# Output_Drivers1.net
KiCad netlist of a schematic drawn in Altium Designer
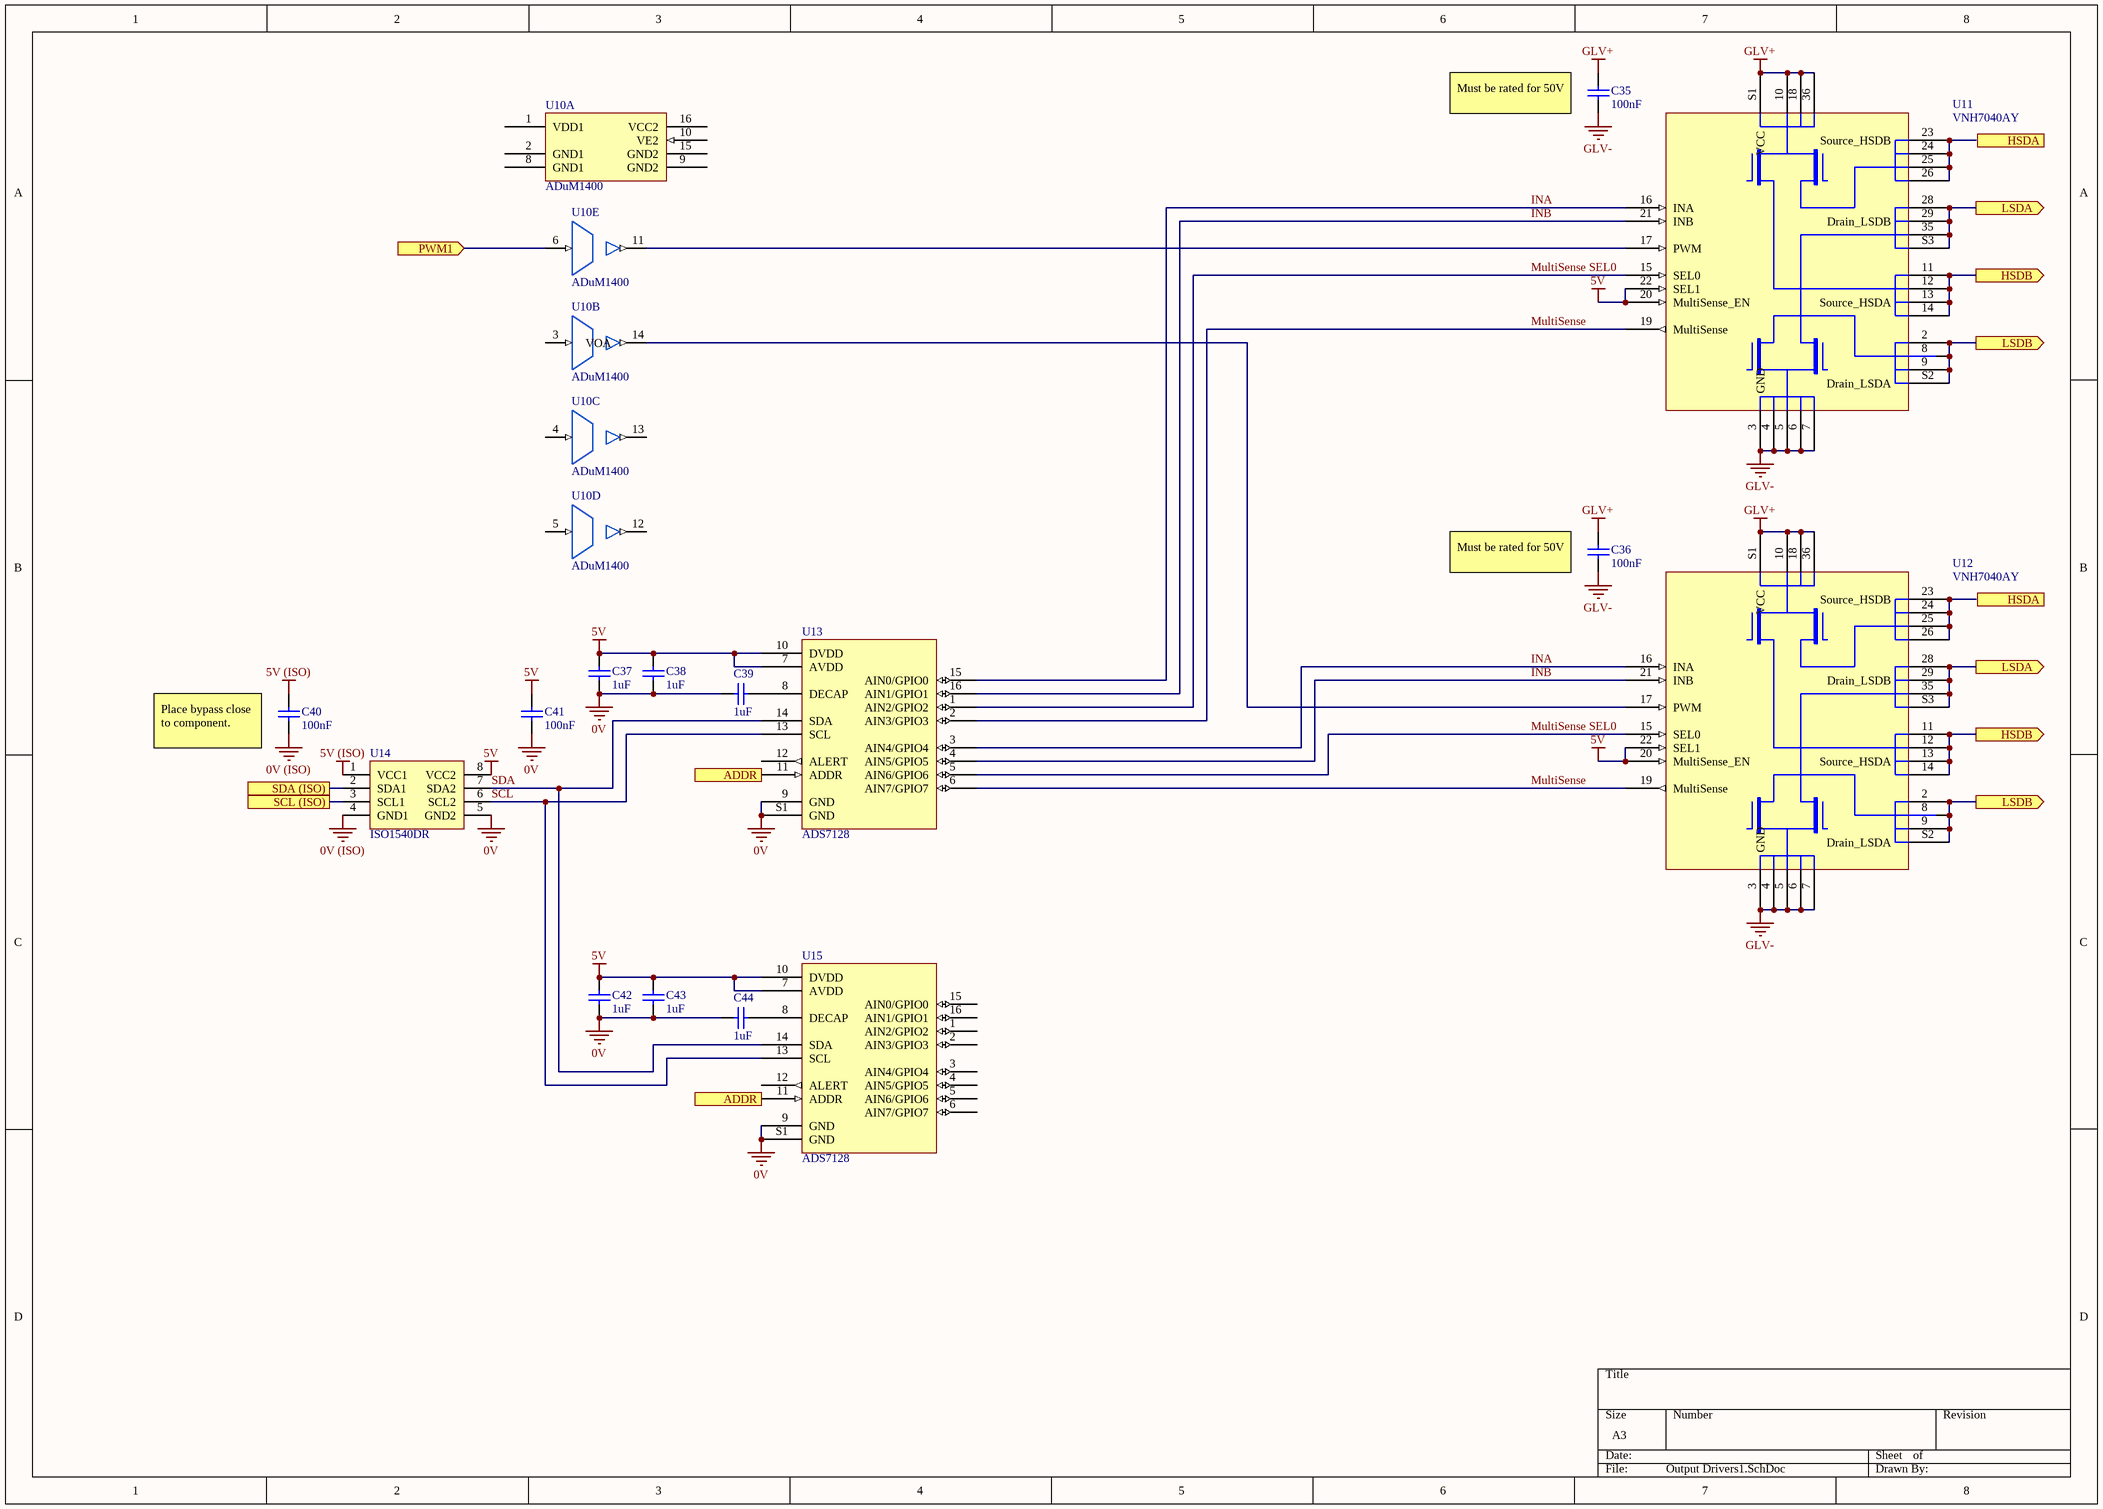
[diagram p0: Output Drivers1.SchDoc]

(export (version "E")
  (design (tool "Eeschema 10.0.6"))
  (components
    (comp (ref "C35")
      (value "100nF")
      (footprint "0805")
      (fields
        (field (name "PART NUMBER") "GCM21BR71E104KA37L")
        (field (name "TOLERANCE") "10%")
        (field (name "MANUFACTURER") "muRata")
      )
      (libsource (lib "ts_20-standard-library") (part "Capacitor"))
    )
    (comp (ref "C36")
      (value "100nF")
      (footprint "0805")
      (fields
        (field (name "PART NUMBER") "GCM21BR71E104KA37L")
        (field (name "TOLERANCE") "10%")
        (field (name "MANUFACTURER") "muRata")
      )
      (libsource (lib "ts_20-standard-library") (part "Capacitor"))
    )
    (comp (ref "C37")
      (value "1uF")
      (footprint "0805")
      (fields
        (field (name "PART NUMBER") "AC0805KKX7R8BB105")
        (field (name "TOLERANCE") "10%")
        (field (name "MANUFACTURER") "YAGEO")
      )
      (libsource (lib "ts_20-standard-library") (part "Capacitor"))
    )
    (comp (ref "C38")
      (value "1uF")
      (footprint "0805")
      (fields
        (field (name "PART NUMBER") "AC0805KKX7R8BB105")
        (field (name "TOLERANCE") "10%")
        (field (name "MANUFACTURER") "YAGEO")
      )
      (libsource (lib "ts_20-standard-library") (part "Capacitor"))
    )
    (comp (ref "C39")
      (value "1uF")
      (footprint "0805")
      (fields
        (field (name "PART NUMBER") "AC0805KKX7R8BB105")
        (field (name "TOLERANCE") "10%")
        (field (name "MANUFACTURER") "YAGEO")
      )
      (libsource (lib "ts_20-standard-library") (part "Capacitor"))
    )
    (comp (ref "C40")
      (value "100nF")
      (footprint "0805")
      (fields
        (field (name "PART NUMBER") "GCM21BR71E104KA37L")
        (field (name "TOLERANCE") "10%")
        (field (name "MANUFACTURER") "muRata")
      )
      (libsource (lib "ts_20-standard-library") (part "Capacitor"))
    )
    (comp (ref "C41")
      (value "100nF")
      (footprint "0805")
      (fields
        (field (name "PART NUMBER") "GCM21BR71E104KA37L")
        (field (name "TOLERANCE") "10%")
        (field (name "MANUFACTURER") "muRata")
      )
      (libsource (lib "ts_20-standard-library") (part "Capacitor"))
    )
    (comp (ref "C42")
      (value "1uF")
      (footprint "0805")
      (fields
        (field (name "PART NUMBER") "AC0805KKX7R8BB105")
        (field (name "TOLERANCE") "10%")
        (field (name "MANUFACTURER") "YAGEO")
      )
      (libsource (lib "ts_20-standard-library") (part "Capacitor"))
    )
    (comp (ref "C43")
      (value "1uF")
      (footprint "0805")
      (fields
        (field (name "PART NUMBER") "AC0805KKX7R8BB105")
        (field (name "TOLERANCE") "10%")
        (field (name "MANUFACTURER") "YAGEO")
      )
      (libsource (lib "ts_20-standard-library") (part "Capacitor"))
    )
    (comp (ref "C44")
      (value "1uF")
      (footprint "0805")
      (fields
        (field (name "PART NUMBER") "AC0805KKX7R8BB105")
        (field (name "TOLERANCE") "10%")
        (field (name "MANUFACTURER") "YAGEO")
      )
      (libsource (lib "ts_20-standard-library") (part "Capacitor"))
    )
    (comp (ref "U10")
      (value "ADuM1400")
      (footprint "AD 16-SOIC")
      (fields
        (field (name "MANUFACTURER") "Analog Devices")
        (field (name "DIGIKEY PART NUMBER") "ADUM1400WSRWZ-ND")
      )
      (libsource (lib "ts_20-standard-library") (part "ADuM1400"))
    )
    (comp (ref "U11")
      (value "VNH7040AY")
      (footprint "ST PowerSSO-36")
      (description "Motor Driver Power MOSFET PWM PowerSSO-36 TP")
      (fields
        (field (name "MANUFACTURER") "STMicroelectronics")
        (field (name "DIGIKEY PART NUMBER") "497-17631-1-ND")
      )
      (libsource (lib "ts_20-standard-library") (part "VNH7040AY"))
    )
    (comp (ref "U12")
      (value "VNH7040AY")
      (footprint "ST PowerSSO-36")
      (description "Motor Driver Power MOSFET PWM PowerSSO-36 TP")
      (fields
        (field (name "MANUFACTURER") "STMicroelectronics")
        (field (name "DIGIKEY PART NUMBER") "497-17631-1-ND")
      )
      (libsource (lib "ts_20-standard-library") (part "VNH7040AY"))
    )
    (comp (ref "U13")
      (value "ADS7128")
      (footprint "TI 16-WQFN")
      (description "12 Bit Analog to Digital Converter 8 Input 1 SAR 16-WQFN (3x3)")
      (fields
        (field (name "MANUFACTURER") "Texas Instruments")
        (field (name "DIGIKEY PART NUMBER") "296-ADS7128IRTERCT-ND")
      )
      (libsource (lib "ts_20-standard-library") (part "ADS7128"))
    )
    (comp (ref "U14")
      (value "ISO1540DR")
      (footprint "TI 8-SOIC")
      (description "I2C Digital Isolator (Multichannel)")
      (fields
        (field (name "MANUFACTURER") "Texas Instruments")
        (field (name "DIGIKEY PART NUMBER") "296-34871-1-ND")
      )
      (libsource (lib "ts_20-standard-library") (part "ISO1540DR"))
    )
    (comp (ref "U15")
      (value "ADS7128")
      (footprint "TI 16-WQFN")
      (description "12 Bit Analog to Digital Converter 8 Input 1 SAR 16-WQFN (3x3)")
      (fields
        (field (name "MANUFACTURER") "Texas Instruments")
        (field (name "DIGIKEY PART NUMBER") "296-ADS7128IRTERCT-ND")
      )
      (libsource (lib "ts_20-standard-library") (part "ADS7128"))
    )
  )
  (nets
    (net (code "1") (name "/ADDR") (class "Default")
      (node (ref "U13") (pin "11") (pinfunction "ADDR_11") (pintype "input"))
      (node (ref "U15") (pin "11") (pinfunction "ADDR_11") (pintype "input"))
    )
    (net (code "3") (name "/HSDB") (class "Default")
      (node (ref "U11") (pin "11") (pinfunction "Source_HSDA_11") (pintype "power_in"))
      (node (ref "U11") (pin "12") (pinfunction "Source_HSDA_12") (pintype "power_in"))
      (node (ref "U11") (pin "13") (pinfunction "Source_HSDA_13") (pintype "power_in"))
      (node (ref "U11") (pin "14") (pinfunction "Source_HSDA_14") (pintype "power_in"))
      (node (ref "U12") (pin "11") (pinfunction "Source_HSDA_11") (pintype "power_in"))
      (node (ref "U12") (pin "12") (pinfunction "Source_HSDA_12") (pintype "power_in"))
      (node (ref "U12") (pin "13") (pinfunction "Source_HSDA_13") (pintype "power_in"))
      (node (ref "U12") (pin "14") (pinfunction "Source_HSDA_14") (pintype "power_in"))
    )
    (net (code "4") (name "/INA") (class "Default")
      (node (ref "U11") (pin "16") (pinfunction "INA_16") (pintype "input"))
      (node (ref "U12") (pin "16") (pinfunction "INA_16") (pintype "input"))
      (node (ref "U13") (pin "15") (pinfunction "AIN0/GPIO0_15") (pintype "bidirectional"))
      (node (ref "U13") (pin "3") (pinfunction "AIN4/GPIO4_3") (pintype "bidirectional"))
    )
    (net (code "5") (name "/INB") (class "Default")
      (node (ref "U11") (pin "21") (pinfunction "INB_21") (pintype "input"))
      (node (ref "U12") (pin "21") (pinfunction "INB_21") (pintype "input"))
      (node (ref "U13") (pin "16") (pinfunction "AIN1/GPIO1_16") (pintype "bidirectional"))
      (node (ref "U13") (pin "4") (pinfunction "AIN5/GPIO5_4") (pintype "bidirectional"))
    )
    (net (code "6") (name "/LSDA") (class "Default")
      (node (ref "U11") (pin "28") (pinfunction "Drain_LSDB_28") (pintype "power_in"))
      (node (ref "U11") (pin "29") (pinfunction "Drain_LSDB_29") (pintype "power_in"))
      (node (ref "U11") (pin "35") (pinfunction "Drain_LSDB_35") (pintype "power_in"))
      (node (ref "U11") (pin "S3") (pinfunction "Drain_LSDB_S3") (pintype "power_in"))
      (node (ref "U12") (pin "28") (pinfunction "Drain_LSDB_28") (pintype "power_in"))
      (node (ref "U12") (pin "29") (pinfunction "Drain_LSDB_29") (pintype "power_in"))
      (node (ref "U12") (pin "35") (pinfunction "Drain_LSDB_35") (pintype "power_in"))
      (node (ref "U12") (pin "S3") (pinfunction "Drain_LSDB_S3") (pintype "power_in"))
    )
    (net (code "7") (name "/LSDB") (class "Default")
      (node (ref "U11") (pin "2") (pinfunction "Drain_LSDA_2") (pintype "power_in"))
      (node (ref "U11") (pin "8") (pinfunction "Drain_LSDA_8") (pintype "power_in"))
      (node (ref "U11") (pin "9") (pinfunction "Drain_LSDA_9") (pintype "power_in"))
      (node (ref "U11") (pin "S2") (pinfunction "Drain_LSDA_S2") (pintype "power_in"))
      (node (ref "U12") (pin "2") (pinfunction "Drain_LSDA_2") (pintype "power_in"))
      (node (ref "U12") (pin "8") (pinfunction "Drain_LSDA_8") (pintype "power_in"))
      (node (ref "U12") (pin "9") (pinfunction "Drain_LSDA_9") (pintype "power_in"))
      (node (ref "U12") (pin "S2") (pinfunction "Drain_LSDA_S2") (pintype "power_in"))
    )
    (net (code "8") (name "/MultiSense") (class "Default")
      (node (ref "U11") (pin "19") (pinfunction "MultiSense_19") (pintype "output"))
      (node (ref "U12") (pin "19") (pinfunction "MultiSense_19") (pintype "output"))
      (node (ref "U13") (pin "2") (pinfunction "AIN3/GPIO3_2") (pintype "bidirectional"))
      (node (ref "U13") (pin "6") (pinfunction "AIN7/GPIO7_6") (pintype "bidirectional"))
    )
    (net (code "9") (name "/MultiSense SEL0") (class "Default")
      (node (ref "U11") (pin "15") (pinfunction "SEL0_15") (pintype "input"))
      (node (ref "U12") (pin "15") (pinfunction "SEL0_15") (pintype "input"))
      (node (ref "U13") (pin "1") (pinfunction "AIN2/GPIO2_1") (pintype "bidirectional"))
      (node (ref "U13") (pin "5") (pinfunction "AIN6/GPIO6_5") (pintype "bidirectional"))
    )
    (net (code "10") (name "/PWM1") (class "Default")
      (node (ref "U10") (pin "6") (pinfunction "VID_6") (pintype "input"))
    )
    (net (code "11") (name "/SCL") (class "Default")
      (node (ref "U13") (pin "13") (pinfunction "SCL_13") (pintype "passive"))
      (node (ref "U14") (pin "6") (pinfunction "SCL2_6") (pintype "power_in"))
      (node (ref "U15") (pin "13") (pinfunction "SCL_13") (pintype "passive"))
    )
    (net (code "12") (name "/SCL (ISO)") (class "Default")
      (node (ref "U14") (pin "3") (pinfunction "SCL1_3") (pintype "power_in"))
    )
    (net (code "13") (name "/SDA") (class "Default")
      (node (ref "U13") (pin "14") (pinfunction "SDA_14") (pintype "passive"))
      (node (ref "U14") (pin "7") (pinfunction "SDA2_7") (pintype "power_in"))
      (node (ref "U15") (pin "14") (pinfunction "SDA_14") (pintype "passive"))
    )
    (net (code "14") (name "/SDA (ISO)") (class "Default")
      (node (ref "U14") (pin "2") (pinfunction "SDA1_2") (pintype "power_in"))
    )
    (net (code "15") (name "0V") (class "Default")
      (node (ref "C37") (pin "1") (pinfunction "1_1") (pintype "passive"))
      (node (ref "C38") (pin "1") (pinfunction "1_1") (pintype "passive"))
      (node (ref "C39") (pin "2") (pinfunction "2_2") (pintype "passive"))
      (node (ref "C41") (pin "1") (pinfunction "1_1") (pintype "passive"))
      (node (ref "C42") (pin "1") (pinfunction "1_1") (pintype "passive"))
      (node (ref "C43") (pin "1") (pinfunction "1_1") (pintype "passive"))
      (node (ref "C44") (pin "2") (pinfunction "2_2") (pintype "passive"))
      (node (ref "U13") (pin "9") (pinfunction "GND_9") (pintype "power_in"))
      (node (ref "U13") (pin "S1") (pinfunction "GND_S1") (pintype "power_in"))
      (node (ref "U14") (pin "5") (pinfunction "GND2_5") (pintype "power_in"))
      (node (ref "U15") (pin "9") (pinfunction "GND_9") (pintype "power_in"))
      (node (ref "U15") (pin "S1") (pinfunction "GND_S1") (pintype "power_in"))
    )
    (net (code "16") (name "0V (ISO)") (class "Default")
      (node (ref "C40") (pin "1") (pinfunction "1_1") (pintype "passive"))
      (node (ref "U14") (pin "4") (pinfunction "GND1_4") (pintype "power_in"))
    )
    (net (code "17") (name "5V") (class "Default")
      (node (ref "C37") (pin "2") (pinfunction "2_2") (pintype "passive"))
      (node (ref "C38") (pin "2") (pinfunction "2_2") (pintype "passive"))
      (node (ref "C41") (pin "2") (pinfunction "2_2") (pintype "passive"))
      (node (ref "C42") (pin "2") (pinfunction "2_2") (pintype "passive"))
      (node (ref "C43") (pin "2") (pinfunction "2_2") (pintype "passive"))
      (node (ref "U11") (pin "20") (pinfunction "MultiSense_EN_20") (pintype "input"))
      (node (ref "U11") (pin "22") (pinfunction "SEL1_22") (pintype "input"))
      (node (ref "U12") (pin "20") (pinfunction "MultiSense_EN_20") (pintype "input"))
      (node (ref "U12") (pin "22") (pinfunction "SEL1_22") (pintype "input"))
      (node (ref "U13") (pin "10") (pinfunction "DVDD_10") (pintype "power_in"))
      (node (ref "U13") (pin "7") (pinfunction "AVDD_7") (pintype "power_in"))
      (node (ref "U14") (pin "8") (pinfunction "VCC2_8") (pintype "power_in"))
      (node (ref "U15") (pin "10") (pinfunction "DVDD_10") (pintype "power_in"))
      (node (ref "U15") (pin "7") (pinfunction "AVDD_7") (pintype "power_in"))
    )
    (net (code "18") (name "5V (ISO)") (class "Default")
      (node (ref "C40") (pin "2") (pinfunction "2_2") (pintype "passive"))
      (node (ref "U14") (pin "1") (pinfunction "VCC1_1") (pintype "power_in"))
    )
    (net (code "19") (name "GLV+") (class "Default")
      (node (ref "C35") (pin "2") (pinfunction "2_2") (pintype "passive"))
      (node (ref "C36") (pin "2") (pinfunction "2_2") (pintype "passive"))
      (node (ref "U11") (pin "10") (pinfunction "VCC_10") (pintype "power_in"))
      (node (ref "U11") (pin "18") (pinfunction "VCC_18") (pintype "power_in"))
      (node (ref "U11") (pin "36") (pinfunction "VCC_36") (pintype "power_in"))
      (node (ref "U11") (pin "S1") (pinfunction "VCC_S1") (pintype "power_in"))
      (node (ref "U12") (pin "10") (pinfunction "VCC_10") (pintype "power_in"))
      (node (ref "U12") (pin "18") (pinfunction "VCC_18") (pintype "power_in"))
      (node (ref "U12") (pin "36") (pinfunction "VCC_36") (pintype "power_in"))
      (node (ref "U12") (pin "S1") (pinfunction "VCC_S1") (pintype "power_in"))
    )
    (net (code "20") (name "GLV-") (class "Default")
      (node (ref "C35") (pin "1") (pinfunction "1_1") (pintype "passive"))
      (node (ref "C36") (pin "1") (pinfunction "1_1") (pintype "passive"))
      (node (ref "U11") (pin "3") (pinfunction "GND_3") (pintype "power_in"))
      (node (ref "U11") (pin "4") (pinfunction "GND_4") (pintype "power_in"))
      (node (ref "U11") (pin "5") (pinfunction "GND_5") (pintype "power_in"))
      (node (ref "U11") (pin "6") (pinfunction "GND_6") (pintype "power_in"))
      (node (ref "U11") (pin "7") (pinfunction "GND_7") (pintype "power_in"))
      (node (ref "U12") (pin "3") (pinfunction "GND_3") (pintype "power_in"))
      (node (ref "U12") (pin "4") (pinfunction "GND_4") (pintype "power_in"))
      (node (ref "U12") (pin "5") (pinfunction "GND_5") (pintype "power_in"))
      (node (ref "U12") (pin "6") (pinfunction "GND_6") (pintype "power_in"))
      (node (ref "U12") (pin "7") (pinfunction "GND_7") (pintype "power_in"))
    )
    (net (code "21") (name "Net-(U10B-VOA)") (class "Default")
      (node (ref "U10") (pin "14") (pinfunction "VOA_14") (pintype "output"))
      (node (ref "U12") (pin "17") (pinfunction "PWM_17") (pintype "input"))
    )
    (net (code "22") (name "Net-(U10E-VOD)") (class "Default")
      (node (ref "U10") (pin "11") (pinfunction "VOD_11") (pintype "output"))
      (node (ref "U11") (pin "17") (pinfunction "PWM_17") (pintype "input"))
    )
    (net (code "23") (name "Net-(U11-Source_HSDB-Pad23)") (class "Default")
      (node (ref "U11") (pin "23") (pinfunction "Source_HSDB_23") (pintype "power_in"))
      (node (ref "U11") (pin "24") (pinfunction "Source_HSDB_24") (pintype "power_in"))
      (node (ref "U11") (pin "25") (pinfunction "Source_HSDB_25") (pintype "power_in"))
      (node (ref "U11") (pin "26") (pinfunction "Source_HSDB_26") (pintype "power_in"))
    )
    (net (code "24") (name "Net-(U12-Source_HSDB-Pad23)") (class "Default")
      (node (ref "U12") (pin "23") (pinfunction "Source_HSDB_23") (pintype "power_in"))
      (node (ref "U12") (pin "24") (pinfunction "Source_HSDB_24") (pintype "power_in"))
      (node (ref "U12") (pin "25") (pinfunction "Source_HSDB_25") (pintype "power_in"))
      (node (ref "U12") (pin "26") (pinfunction "Source_HSDB_26") (pintype "power_in"))
    )
    (net (code "25") (name "Net-(U13-DECAP)") (class "Default")
      (node (ref "C39") (pin "1") (pinfunction "1_1") (pintype "passive"))
      (node (ref "U13") (pin "8") (pinfunction "DECAP_8") (pintype "power_in"))
    )
    (net (code "26") (name "Net-(U15-DECAP)") (class "Default")
      (node (ref "C44") (pin "1") (pinfunction "1_1") (pintype "passive"))
      (node (ref "U15") (pin "8") (pinfunction "DECAP_8") (pintype "power_in"))
    )
    (net (code "27") (name "unconnected-(U10A-GND1-Pad2)") (class "Default")
      (node (ref "U10") (pin "2") (pinfunction "GND1_2") (pintype "power_in"))
    )
    (net (code "28") (name "unconnected-(U10A-GND1-Pad8)") (class "Default")
      (node (ref "U10") (pin "8") (pinfunction "GND1_8") (pintype "power_in"))
    )
    (net (code "29") (name "unconnected-(U10A-GND2-Pad9)") (class "Default")
      (node (ref "U10") (pin "9") (pinfunction "GND2_9") (pintype "power_in"))
    )
    (net (code "30") (name "unconnected-(U10A-GND2-Pad15)") (class "Default")
      (node (ref "U10") (pin "15") (pinfunction "GND2_15") (pintype "power_in"))
    )
    (net (code "31") (name "unconnected-(U10A-VCC2-Pad16)") (class "Default")
      (node (ref "U10") (pin "16") (pinfunction "VCC2_16") (pintype "power_in"))
    )
    (net (code "32") (name "unconnected-(U10A-VDD1-Pad1)") (class "Default")
      (node (ref "U10") (pin "1") (pinfunction "VDD1_1") (pintype "power_in"))
    )
    (net (code "33") (name "unconnected-(U10A-VE2-Pad10)") (class "Default")
      (node (ref "U10") (pin "10") (pinfunction "VE2_10") (pintype "input"))
    )
    (net (code "34") (name "unconnected-(U10B-VIA-Pad3)") (class "Default")
      (node (ref "U10") (pin "3") (pinfunction "VIA_3") (pintype "input"))
    )
    (net (code "35") (name "unconnected-(U10C-VIB-Pad4)") (class "Default")
      (node (ref "U10") (pin "4") (pinfunction "VIB_4") (pintype "input"))
    )
    (net (code "36") (name "unconnected-(U10C-VOB-Pad13)") (class "Default")
      (node (ref "U10") (pin "13") (pinfunction "VOB_13") (pintype "output"))
    )
    (net (code "37") (name "unconnected-(U10D-VIC-Pad5)") (class "Default")
      (node (ref "U10") (pin "5") (pinfunction "VIC_5") (pintype "input"))
    )
    (net (code "38") (name "unconnected-(U10D-VOC-Pad12)") (class "Default")
      (node (ref "U10") (pin "12") (pinfunction "VOC_12") (pintype "output"))
    )
    (net (code "39") (name "unconnected-(U13-ALERT-Pad12)") (class "Default")
      (node (ref "U13") (pin "12") (pinfunction "ALERT_12") (pintype "output"))
    )
    (net (code "40") (name "unconnected-(U15-AIN0{slash}GPIO0-Pad15)") (class "Default")
      (node (ref "U15") (pin "15") (pinfunction "AIN0/GPIO0_15") (pintype "bidirectional"))
    )
    (net (code "41") (name "unconnected-(U15-AIN1{slash}GPIO1-Pad16)") (class "Default")
      (node (ref "U15") (pin "16") (pinfunction "AIN1/GPIO1_16") (pintype "bidirectional"))
    )
    (net (code "42") (name "unconnected-(U15-AIN2{slash}GPIO2-Pad1)") (class "Default")
      (node (ref "U15") (pin "1") (pinfunction "AIN2/GPIO2_1") (pintype "bidirectional"))
    )
    (net (code "43") (name "unconnected-(U15-AIN3{slash}GPIO3-Pad2)") (class "Default")
      (node (ref "U15") (pin "2") (pinfunction "AIN3/GPIO3_2") (pintype "bidirectional"))
    )
    (net (code "44") (name "unconnected-(U15-AIN4{slash}GPIO4-Pad3)") (class "Default")
      (node (ref "U15") (pin "3") (pinfunction "AIN4/GPIO4_3") (pintype "bidirectional"))
    )
    (net (code "45") (name "unconnected-(U15-AIN5{slash}GPIO5-Pad4)") (class "Default")
      (node (ref "U15") (pin "4") (pinfunction "AIN5/GPIO5_4") (pintype "bidirectional"))
    )
    (net (code "46") (name "unconnected-(U15-AIN6{slash}GPIO6-Pad5)") (class "Default")
      (node (ref "U15") (pin "5") (pinfunction "AIN6/GPIO6_5") (pintype "bidirectional"))
    )
    (net (code "47") (name "unconnected-(U15-AIN7{slash}GPIO7-Pad6)") (class "Default")
      (node (ref "U15") (pin "6") (pinfunction "AIN7/GPIO7_6") (pintype "bidirectional"))
    )
    (net (code "48") (name "unconnected-(U15-ALERT-Pad12)") (class "Default")
      (node (ref "U15") (pin "12") (pinfunction "ALERT_12") (pintype "output"))
    )
  )
)
